# PWM-SWITCH.net
KiCad netlist of a schematic drawn in Altium Designer
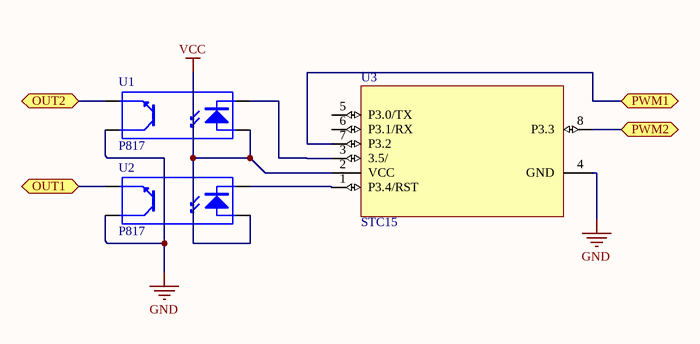
[diagram p0: PWM-SWITCH.SchDoc]

(export (version "E")
  (design (tool "Eeschema 10.0.6"))
  (components
    (comp (ref "U1")
      (value "P817")
      (footprint "DIP-4")
      (description "4-Pin Phototransistor Optocoupler")
      (fields (field (name "PUBLISHER") "Altium Limited"))
      (libsource (lib "Miscellaneous Devices") (part "Optoisolator1"))
    )
    (comp (ref "U2")
      (value "P817")
      (footprint "DIP-4")
      (description "4-Pin Phototransistor Optocoupler")
      (fields (field (name "PUBLISHER") "Altium Limited"))
      (libsource (lib "Miscellaneous Devices") (part "Optoisolator1"))
    )
    (comp (ref "U3")
      (value "STC15")
      (footprint "8P3")
      (description "8-Bit AVR Microcontroller with 1K Byte of Flash Memory")
      (fields (field (name "PUBLISHER") "Altium Limited"))
      (libsource (lib "Atmel Microcontroller 8-Bit AVR") (part "ATtiny15L-1PC"))
    )
  )
  (nets
    (net (code "1") (name "/OUT1") (class "Default")
      (node (ref "U2") (pin "3") (pinfunction "E_3") (pintype "passive"))
    )
    (net (code "2") (name "/OUT2") (class "Default")
      (node (ref "U1") (pin "3") (pinfunction "E_3") (pintype "passive"))
    )
    (net (code "3") (name "/PWM1") (class "Default")
      (node (ref "U3") (pin "7") (pinfunction "P3.2_7") (pintype "bidirectional"))
    )
    (net (code "4") (name "/PWM2") (class "Default")
      (node (ref "U3") (pin "8") (pinfunction "P3.3_8") (pintype "bidirectional"))
    )
    (net (code "5") (name "GND") (class "Default")
      (node (ref "U1") (pin "4") (pinfunction "C_4") (pintype "passive"))
      (node (ref "U2") (pin "4") (pinfunction "C_4") (pintype "passive"))
      (node (ref "U3") (pin "4") (pinfunction "GND_4") (pintype "power_in"))
    )
    (net (code "6") (name "Net-(U1-K)") (class "Default")
      (node (ref "U1") (pin "2") (pinfunction "K_2") (pintype "passive"))
      (node (ref "U3") (pin "3") (pinfunction "3.5/_3") (pintype "bidirectional"))
    )
    (net (code "7") (name "Net-(U2-K)") (class "Default")
      (node (ref "U2") (pin "2") (pinfunction "K_2") (pintype "passive"))
      (node (ref "U3") (pin "1") (pinfunction "P3.4/RST_1") (pintype "bidirectional"))
    )
    (net (code "8") (name "VCC") (class "Default")
      (node (ref "U1") (pin "1") (pinfunction "A_1") (pintype "passive"))
      (node (ref "U2") (pin "1") (pinfunction "A_1") (pintype "passive"))
      (node (ref "U3") (pin "2") (pinfunction "VCC_2") (pintype "power_in"))
    )
    (net (code "9") (name "unconnected-(U3-P3.0{slash}TX-Pad5)") (class "Default")
      (node (ref "U3") (pin "5") (pinfunction "P3.0/TX_5") (pintype "bidirectional"))
    )
    (net (code "10") (name "unconnected-(U3-P3.1{slash}RX-Pad6)") (class "Default")
      (node (ref "U3") (pin "6") (pinfunction "P3.1/RX_6") (pintype "bidirectional"))
    )
  )
)
